# BLT_Preliminary_Avionics_Schematic_Brand.net
KiCad netlist of a schematic drawn in EAGLE
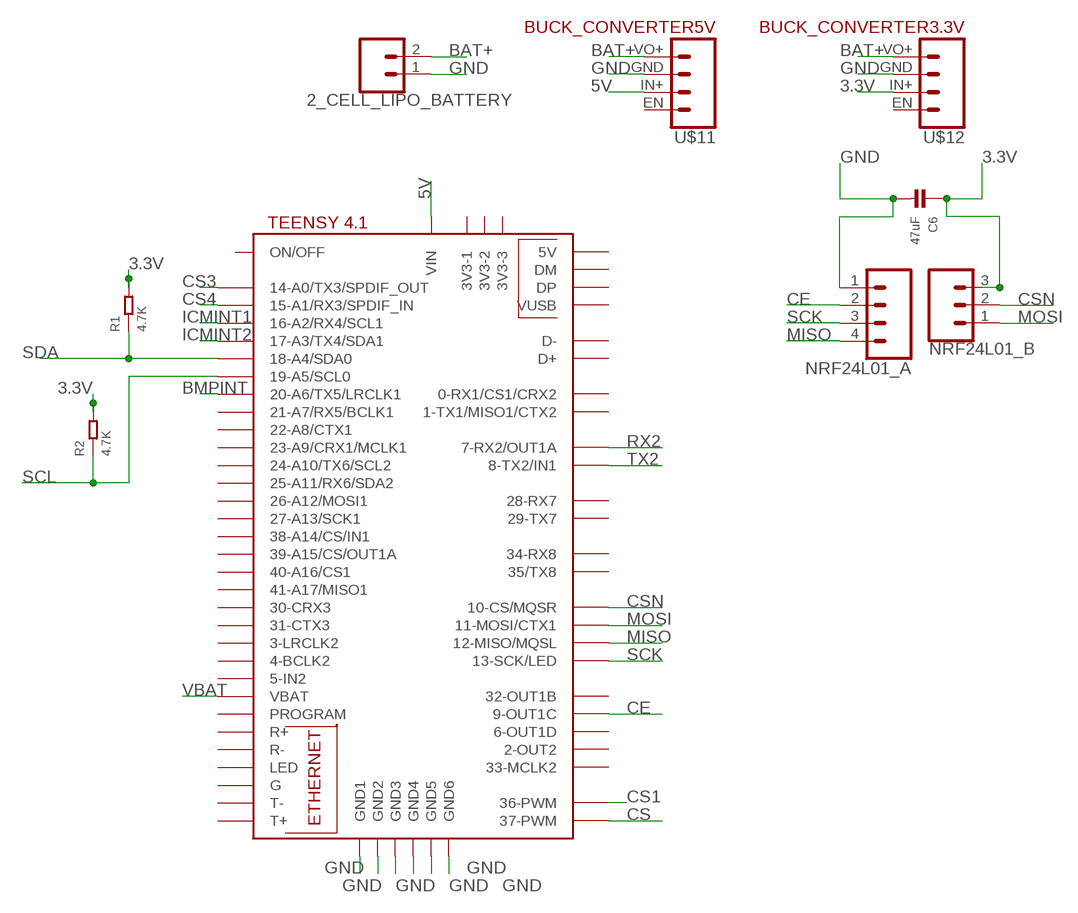
[diagram p0: schematic, sheet 1, part 1 of 2]
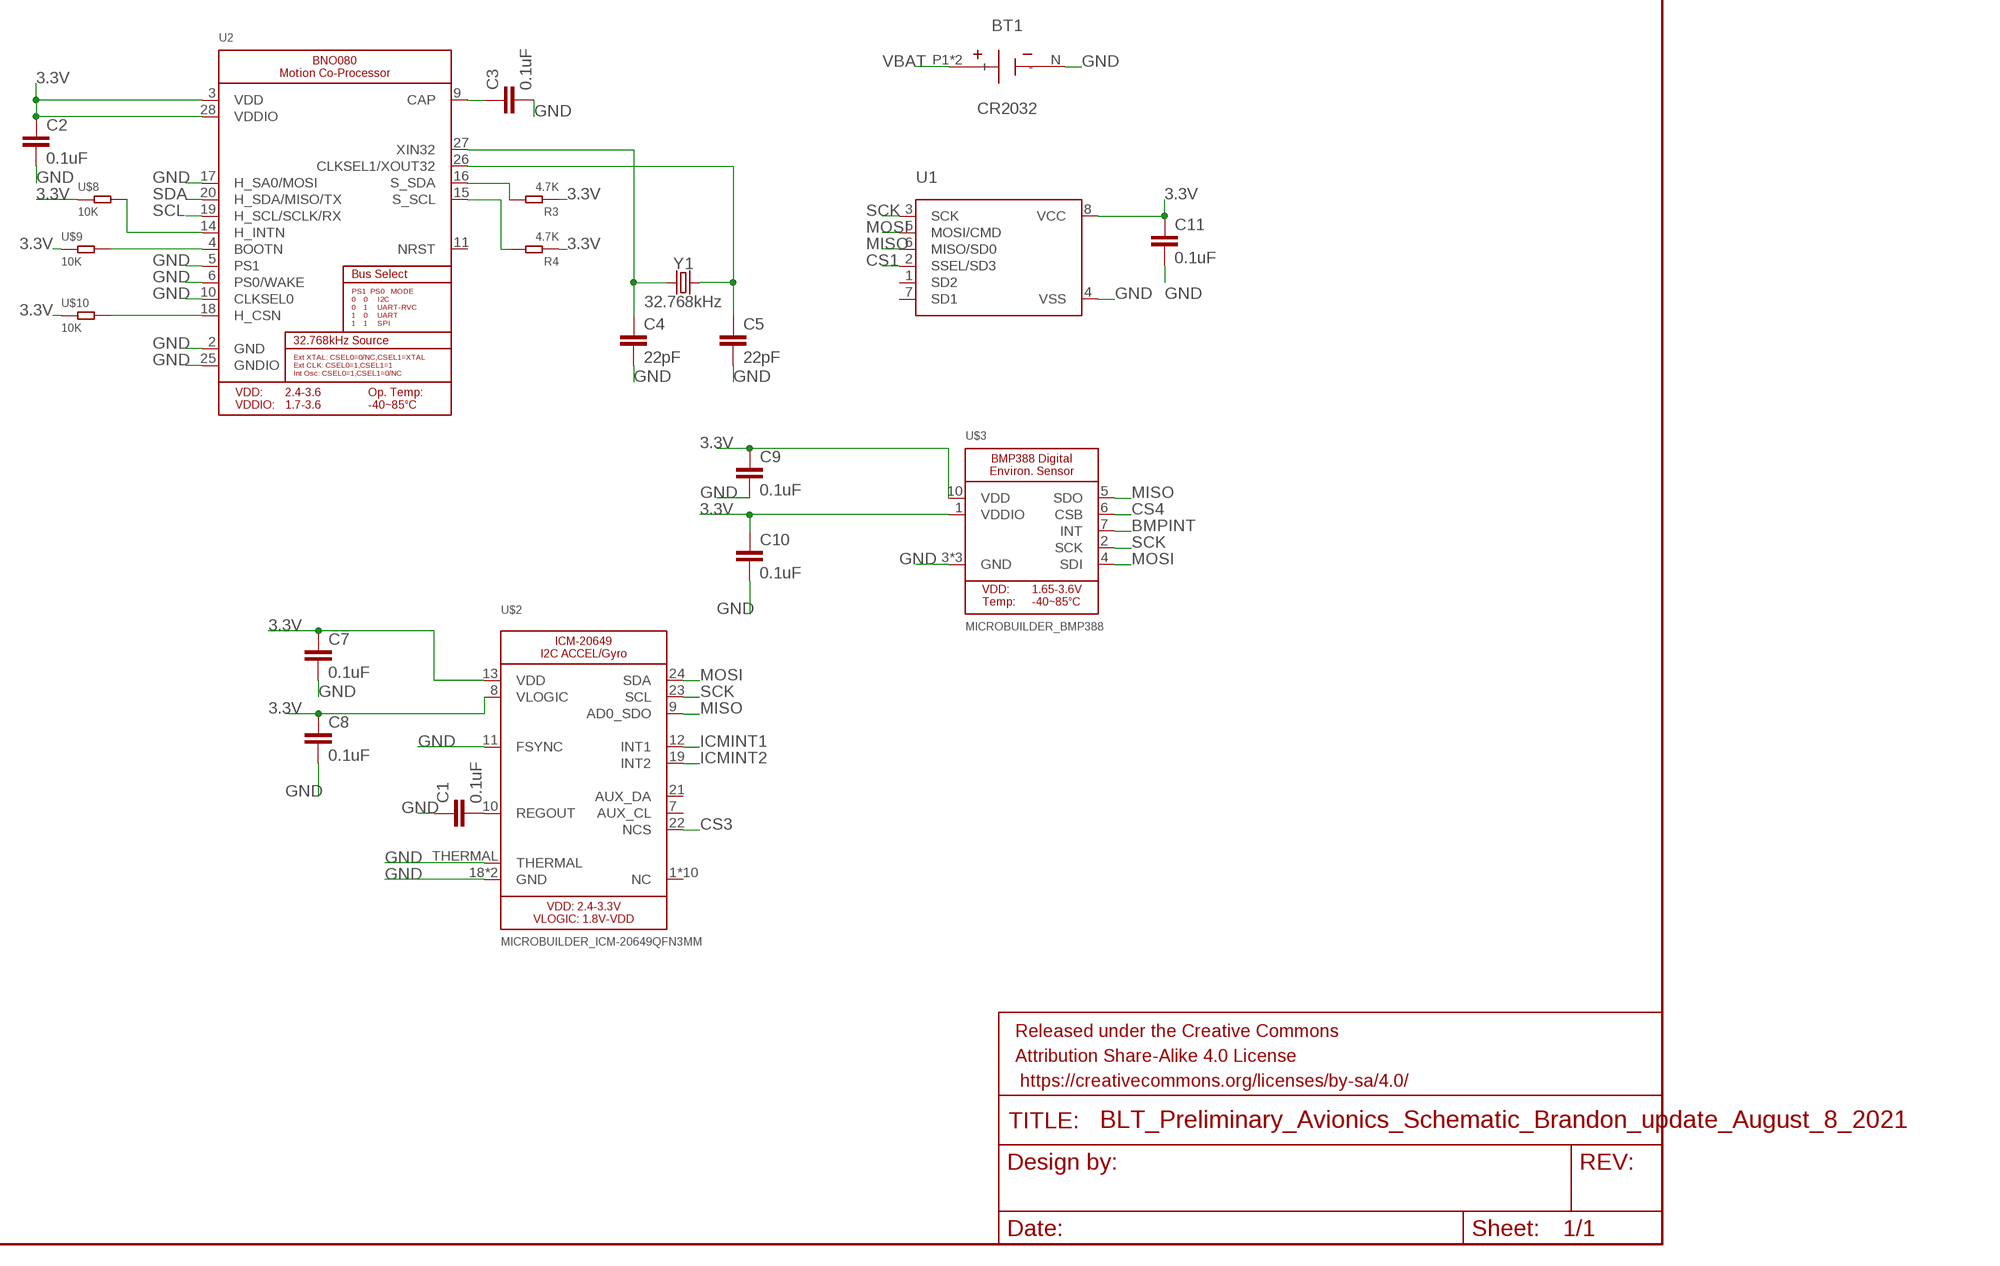
[diagram p1: schematic, sheet 1, part 2 of 2]

(export (version "E")
  (design (tool "Eeschema 10.0.6"))
  (components
    (comp (ref "2_CELL_LIPO_BATTERY")
      (value "CONN_02")
      (footprint "eagle-import:1X02")
      (libsource (lib "eagle-import") (part "CONN_02"))
    )
    (comp (ref "BT1")
      (value "CR2032")
      (footprint "eagle-import:BAT_3003")
      (fields (field (name "MANUFACTURER") "Keystone Electronics") (field (name "MPN") "3003"))
      (libsource (lib "eagle-import") (part "COIN-CELL-THM-3P?--3003CR2032"))
    )
    (comp (ref "C1")
      (value "0.1uF")
      (footprint "eagle-import:0402")
      (libsource (lib "eagle-import") (part "0.1UF-0402-16V-10%"))
    )
    (comp (ref "C2")
      (value "0.1uF")
      (footprint "eagle-import:0402")
      (libsource (lib "eagle-import") (part "0.1UF-0402-16V-10%"))
    )
    (comp (ref "C3")
      (value "0.1uF")
      (footprint "eagle-import:0402")
      (libsource (lib "eagle-import") (part "0.1UF-0402-16V-10%"))
    )
    (comp (ref "C4")
      (value "22pF")
      (footprint "eagle-import:0603")
      (libsource (lib "eagle-import") (part "22PF-0603-50V-5%"))
    )
    (comp (ref "C5")
      (value "22pF")
      (footprint "eagle-import:0603")
      (libsource (lib "eagle-import") (part "22PF-0603-50V-5%"))
    )
    (comp (ref "C6")
      (value "47uF")
      (footprint "eagle-import:0805")
      (libsource (lib "eagle-import") (part "CAP_CERAMIC0805"))
    )
    (comp (ref "C7")
      (value "0.1uF")
      (footprint "eagle-import:0603")
      (libsource (lib "eagle-import") (part "0.1UF-0603-100V-10%"))
    )
    (comp (ref "C8")
      (value "0.1uF")
      (footprint "eagle-import:0603")
      (libsource (lib "eagle-import") (part "0.1UF-0603-100V-10%"))
    )
    (comp (ref "C9")
      (value "0.1uF")
      (footprint "eagle-import:0603")
      (libsource (lib "eagle-import") (part "0.1UF-0603-100V-10%"))
    )
    (comp (ref "C10")
      (value "0.1uF")
      (footprint "eagle-import:0603")
      (libsource (lib "eagle-import") (part "0.1UF-0603-100V-10%"))
    )
    (comp (ref "C11")
      (value "0.1uF")
      (footprint "eagle-import:0603")
      (libsource (lib "eagle-import") (part "0.1UF-0603-100V-10%"))
    )
    (comp (ref "FRAME1")
      (value "FRAME-LEDGER")
      (footprint "eagle-import:CREATIVE_COMMONS")
      (libsource (lib "eagle-import") (part "FRAME-LEDGER"))
    )
    (comp (ref "NRF24L01_A")
      (value "CONN_04")
      (footprint "eagle-import:1X04")
      (libsource (lib "eagle-import") (part "CONN_04"))
    )
    (comp (ref "NRF24L01_B")
      (value "CONN_03")
      (footprint "eagle-import:1X03")
      (libsource (lib "eagle-import") (part "CONN_03"))
    )
    (comp (ref "R1")
      (value "4.7K")
      (footprint "eagle-import:R0402")
      (fields (field (name "MPN") "RC0402JR-074K7L"))
      (libsource (lib "eagle-import") (part "SMD-RES-4.7K-5%-1/16W(0402)"))
    )
    (comp (ref "R2")
      (value "4.7K")
      (footprint "eagle-import:R0402")
      (fields (field (name "MPN") "RC0402JR-074K7L"))
      (libsource (lib "eagle-import") (part "SMD-RES-4.7K-5%-1/16W(0402)"))
    )
    (comp (ref "R3")
      (value "4.7K")
      (footprint "eagle-import:R0402")
      (fields (field (name "MPN") "RC0402JR-074K7L"))
      (libsource (lib "eagle-import") (part "SMD-RES-4.7K-5%-1/16W(0402)"))
    )
    (comp (ref "R4")
      (value "4.7K")
      (footprint "eagle-import:R0402")
      (fields (field (name "MPN") "RC0402JR-074K7L"))
      (libsource (lib "eagle-import") (part "SMD-RES-4.7K-5%-1/16W(0402)"))
    )
    (comp (ref "U$1")
      (value "TEENSY41")
      (footprint "eagle-import:TEENSY41")
      (libsource (lib "eagle-import") (part "TEENSY41"))
    )
    (comp (ref "U$2")
      (value "MICROBUILDER_ICM-20649QFN3MM")
      (footprint "eagle-import:MICROBUILDER_QFN24_3MM")
      (libsource (lib "eagle-import") (part "MICROBUILDER_ICM-20649QFN3MM"))
    )
    (comp (ref "U$3")
      (value "MICROBUILDER_BMP388")
      (footprint "eagle-import:MICROBUILDER_BMP388")
      (libsource (lib "eagle-import") (part "MICROBUILDER_BMP388"))
    )
    (comp (ref "U$8")
      (value "10K")
      (footprint "eagle-import:R0402")
      (fields (field (name "MPN") "RC0402JR-0710KL"))
      (libsource (lib "eagle-import") (part "SMD-RES-10K-5%-1/(0402)"))
    )
    (comp (ref "U$9")
      (value "10K")
      (footprint "eagle-import:R0402")
      (fields (field (name "MPN") "RC0402JR-0710KL"))
      (libsource (lib "eagle-import") (part "SMD-RES-10K-5%-1/(0402)"))
    )
    (comp (ref "U$10")
      (value "10K")
      (footprint "eagle-import:R0402")
      (fields (field (name "MPN") "RC0402JR-0710KL"))
      (libsource (lib "eagle-import") (part "SMD-RES-10K-5%-1/(0402)"))
    )
    (comp (ref "U$11")
      (value "BUCK_CONVERTER5V")
      (footprint "eagle-import:1X04")
      (fields (field (name "VOLTAGE") "5V"))
      (libsource (lib "eagle-import") (part "BUCK_CONVERTER5V"))
    )
    (comp (ref "U$12")
      (value "BUCK_CONVERTER3.3V")
      (footprint "eagle-import:1X04")
      (fields (field (name "VOLTAGE") "3.3V"))
      (libsource (lib "eagle-import") (part "BUCK_CONVERTER3.3V"))
    )
    (comp (ref "U1")
      (value "MICROBUILDER_SMT_SDCARD_8PIN")
      (footprint "eagle-import:MICROBUILDER_LGA8_8X6")
      (libsource (lib "eagle-import") (part "MICROBUILDER_SMT_SDCARD_8PIN"))
    )
    (comp (ref "U2")
      (value "MICROBUILDER_BNO080")
      (footprint "eagle-import:MICROBUILDER_BNO080")
      (libsource (lib "eagle-import") (part "MICROBUILDER_BNO080"))
    )
    (comp (ref "Y1")
      (value "32.768kHz")
      (footprint "eagle-import:CRYSTAL-SMD-3.2X1.5MM")
      (libsource (lib "eagle-import") (part "CRYSTAL-32.768KHZSMD-3.2X1.5"))
    )
  )
  (nets
    (net (code "1") (name "/3.3V") (class "Default")
      (node (ref "C10") (pin "1") (pinfunction "1_1") (pintype "passive"))
      (node (ref "C11") (pin "1") (pinfunction "1_1") (pintype "passive"))
      (node (ref "C2") (pin "1") (pinfunction "1_1") (pintype "passive"))
      (node (ref "C6") (pin "1") (pinfunction "P$1_1") (pintype "passive"))
      (node (ref "C7") (pin "1") (pinfunction "1_1") (pintype "passive"))
      (node (ref "C8") (pin "1") (pinfunction "1_1") (pintype "passive"))
      (node (ref "C9") (pin "1") (pinfunction "1_1") (pintype "passive"))
      (node (ref "NRF24L01_B") (pin "3") (pinfunction "3_3") (pintype "passive"))
      (node (ref "R1") (pin "2") (pinfunction "2_2") (pintype "passive"))
      (node (ref "R2") (pin "2") (pinfunction "2_2") (pintype "passive"))
      (node (ref "R3") (pin "1") (pinfunction "1_1") (pintype "passive"))
      (node (ref "R4") (pin "1") (pinfunction "1_1") (pintype "passive"))
      (node (ref "U$10") (pin "1") (pinfunction "1_1") (pintype "passive"))
      (node (ref "U$12") (pin "IN+") (pinfunction "IN+_IN+") (pintype "passive"))
      (node (ref "U$2") (pin "13") (pinfunction "VDD_13") (pintype "power_in"))
      (node (ref "U$2") (pin "8") (pinfunction "VLOGIC_8") (pintype "power_in"))
      (node (ref "U$3") (pin "1") (pinfunction "VDDIO_1") (pintype "power_in"))
      (node (ref "U$3") (pin "10") (pinfunction "VDD_10") (pintype "power_in"))
      (node (ref "U$8") (pin "1") (pinfunction "1_1") (pintype "passive"))
      (node (ref "U$9") (pin "1") (pinfunction "1_1") (pintype "passive"))
      (node (ref "U1") (pin "8") (pinfunction "VCC_8") (pintype "power_in"))
      (node (ref "U2") (pin "28") (pinfunction "VDDIO_28") (pintype "power_in"))
      (node (ref "U2") (pin "3") (pinfunction "VDD_3") (pintype "power_in"))
    )
    (net (code "2") (name "/5V") (class "Default")
      (node (ref "U$1") (pin "VIN") (pinfunction "VIN_VIN") (pintype "bidirectional"))
      (node (ref "U$11") (pin "IN+") (pinfunction "IN+_IN+") (pintype "passive"))
    )
    (net (code "3") (name "/BAT+") (class "Default")
      (node (ref "2_CELL_LIPO_BATTERY") (pin "2") (pinfunction "2_2") (pintype "passive"))
      (node (ref "U$11") (pin "VO+") (pinfunction "VO+_VO+") (pintype "passive"))
      (node (ref "U$12") (pin "VO+") (pinfunction "VO+_VO+") (pintype "passive"))
    )
    (net (code "4") (name "/BMPINT") (class "Default")
      (node (ref "U$1") (pin "20-A6/TX5/LRCLK1") (pinfunction "20-A6/TX5/LRCLK1_20-A6/TX5/LRCLK1") (pintype "bidirectional"))
      (node (ref "U$3") (pin "7") (pinfunction "INT_7") (pintype "output"))
    )
    (net (code "5") (name "/CE") (class "Default")
      (node (ref "NRF24L01_A") (pin "2") (pinfunction "2_2") (pintype "passive"))
      (node (ref "U$1") (pin "9-OUT1C") (pinfunction "9-OUT1C_9-OUT1C") (pintype "bidirectional"))
    )
    (net (code "6") (name "/CS") (class "Default")
      (node (ref "U$1") (pin "37-PWM") (pinfunction "37-PWM_37-PWM") (pintype "bidirectional"))
    )
    (net (code "7") (name "/CS1") (class "Default")
      (node (ref "U$1") (pin "36-PWM") (pinfunction "36-PWM_36-PWM") (pintype "bidirectional"))
      (node (ref "U1") (pin "2") (pinfunction "SSEL/SD3_2") (pintype "bidirectional"))
    )
    (net (code "8") (name "/CS3") (class "Default")
      (node (ref "U$1") (pin "14-A0/TX3/SPDIF_OUT") (pinfunction "14-A0/TX3/SPDIF_OUT_14-A0/TX3/SPDIF_OUT") (pintype "bidirectional"))
      (node (ref "U$2") (pin "22") (pinfunction "NCS_22") (pintype "input"))
    )
    (net (code "9") (name "/CS4") (class "Default")
      (node (ref "U$1") (pin "15-A1/RX3/SPDIF_IN") (pinfunction "15-A1/RX3/SPDIF_IN_15-A1/RX3/SPDIF_IN") (pintype "bidirectional"))
      (node (ref "U$3") (pin "6") (pinfunction "CSB_6") (pintype "input"))
    )
    (net (code "10") (name "/CSN") (class "Default")
      (node (ref "NRF24L01_B") (pin "2") (pinfunction "2_2") (pintype "passive"))
      (node (ref "U$1") (pin "10-CS\\MQSR") (pinfunction "10-CS/MQSR_10-CS\\MQSR") (pintype "bidirectional"))
    )
    (net (code "11") (name "/GND") (class "Default")
      (node (ref "2_CELL_LIPO_BATTERY") (pin "1") (pinfunction "1_1") (pintype "passive"))
      (node (ref "BT1") (pin "N") (pinfunction "-_N") (pintype "bidirectional"))
      (node (ref "C1") (pin "1") (pinfunction "1_1") (pintype "passive"))
      (node (ref "C10") (pin "2") (pinfunction "2_2") (pintype "passive"))
      (node (ref "C11") (pin "2") (pinfunction "2_2") (pintype "passive"))
      (node (ref "C2") (pin "2") (pinfunction "2_2") (pintype "passive"))
      (node (ref "C3") (pin "2") (pinfunction "2_2") (pintype "passive"))
      (node (ref "C4") (pin "2") (pinfunction "2_2") (pintype "passive"))
      (node (ref "C5") (pin "2") (pinfunction "2_2") (pintype "passive"))
      (node (ref "C6") (pin "2") (pinfunction "P$2_2") (pintype "passive"))
      (node (ref "C7") (pin "2") (pinfunction "2_2") (pintype "passive"))
      (node (ref "C8") (pin "2") (pinfunction "2_2") (pintype "passive"))
      (node (ref "C9") (pin "2") (pinfunction "2_2") (pintype "passive"))
      (node (ref "NRF24L01_A") (pin "1") (pinfunction "1_1") (pintype "passive"))
      (node (ref "U$1") (pin "GND1") (pinfunction "GND1_GND1") (pintype "bidirectional"))
      (node (ref "U$1") (pin "GND2") (pinfunction "GND2_GND2") (pintype "bidirectional"))
      (node (ref "U$1") (pin "GND3") (pinfunction "GND3_GND3") (pintype "bidirectional"))
      (node (ref "U$1") (pin "GND4") (pinfunction "GND4_GND4") (pintype "bidirectional"))
      (node (ref "U$1") (pin "GND5") (pinfunction "GND5_GND5") (pintype "bidirectional"))
      (node (ref "U$1") (pin "GND6") (pinfunction "GND6_GND6") (pintype "bidirectional"))
      (node (ref "U$11") (pin "GND") (pinfunction "GND_GND") (pintype "passive"))
      (node (ref "U$12") (pin "GND") (pinfunction "GND_GND") (pintype "passive"))
      (node (ref "U$2") (pin "11") (pinfunction "FSYNC_11") (pintype "input"))
      (node (ref "U$2") (pin "18") (pinfunction "GND_18") (pintype "power_in"))
      (node (ref "U$2") (pin "20") (pinfunction "GND_20") (pintype "power_in"))
      (node (ref "U$2") (pin "THERMAL") (pinfunction "THERMAL_THERMAL") (pintype "power_in"))
      (node (ref "U$3") (pin "3") (pinfunction "GND_3") (pintype "power_in"))
      (node (ref "U$3") (pin "8") (pinfunction "GND_8") (pintype "power_in"))
      (node (ref "U$3") (pin "9") (pinfunction "GND_9") (pintype "power_in"))
      (node (ref "U1") (pin "4") (pinfunction "VSS_4") (pintype "power_in"))
      (node (ref "U2") (pin "10") (pinfunction "CLKSEL0_10") (pintype "input"))
      (node (ref "U2") (pin "17") (pinfunction "H_SA0/MOSI_17") (pintype "output"))
      (node (ref "U2") (pin "2") (pinfunction "GND_2") (pintype "power_in"))
      (node (ref "U2") (pin "25") (pinfunction "GNDIO_25") (pintype "power_in"))
      (node (ref "U2") (pin "5") (pinfunction "PS1_5") (pintype "input"))
      (node (ref "U2") (pin "6") (pinfunction "PS0/WAKE_6") (pintype "input"))
    )
    (net (code "12") (name "/ICMINT1") (class "Default")
      (node (ref "U$1") (pin "16-A2/RX4/SCL1") (pinfunction "16-A2/RX4/SCL1_16-A2/RX4/SCL1") (pintype "bidirectional"))
      (node (ref "U$2") (pin "12") (pinfunction "INT1_12") (pintype "output"))
    )
    (net (code "13") (name "/ICMINT2") (class "Default")
      (node (ref "U$1") (pin "17-A3/TX4/SDA1") (pinfunction "17-A3/TX4/SDA1_17-A3/TX4/SDA1") (pintype "bidirectional"))
      (node (ref "U$2") (pin "19") (pinfunction "INT2_19") (pintype "output"))
    )
    (net (code "14") (name "/MISO") (class "Default")
      (node (ref "NRF24L01_A") (pin "4") (pinfunction "4_4") (pintype "passive"))
      (node (ref "U$1") (pin "12-MISO/MQSL") (pinfunction "12-MISO/MQSL_12-MISO/MQSL") (pintype "bidirectional"))
      (node (ref "U$2") (pin "9") (pinfunction "AD0_SDO_9") (pintype "input"))
      (node (ref "U$3") (pin "5") (pinfunction "SDO_5") (pintype "output"))
      (node (ref "U1") (pin "6") (pinfunction "MISO/SD0_6") (pintype "bidirectional"))
    )
    (net (code "15") (name "/MOSI") (class "Default")
      (node (ref "NRF24L01_B") (pin "1") (pinfunction "1_1") (pintype "passive"))
      (node (ref "U$1") (pin "11-MOSI/CTX1") (pinfunction "11-MOSI/CTX1_11-MOSI/CTX1") (pintype "bidirectional"))
      (node (ref "U$2") (pin "24") (pinfunction "SDA_24") (pintype "bidirectional"))
      (node (ref "U$3") (pin "4") (pinfunction "SDI_4") (pintype "input"))
      (node (ref "U1") (pin "5") (pinfunction "MOSI/CMD_5") (pintype "bidirectional"))
    )
    (net (code "16") (name "/RX2") (class "Default")
      (node (ref "U$1") (pin "7-RX2/OUT1A") (pinfunction "7-RX2/OUT1A_7-RX2/OUT1A") (pintype "bidirectional"))
    )
    (net (code "17") (name "/SCK") (class "Default")
      (node (ref "NRF24L01_A") (pin "3") (pinfunction "3_3") (pintype "passive"))
      (node (ref "U$1") (pin "13-SCK/LED") (pinfunction "13-SCK/LED_13-SCK/LED") (pintype "bidirectional"))
      (node (ref "U$2") (pin "23") (pinfunction "SCL_23") (pintype "bidirectional"))
      (node (ref "U$3") (pin "2") (pinfunction "SCK_2") (pintype "input"))
      (node (ref "U1") (pin "3") (pinfunction "SCK_3") (pintype "input"))
    )
    (net (code "18") (name "/SCL") (class "Default")
      (node (ref "R2") (pin "1") (pinfunction "1_1") (pintype "passive"))
      (node (ref "U$1") (pin "19-A5/SCL0") (pinfunction "19-A5/SCL0_19-A5/SCL0") (pintype "bidirectional"))
      (node (ref "U2") (pin "19") (pinfunction "H_SCL/SCLK/RX_19") (pintype "bidirectional"))
    )
    (net (code "19") (name "/SDA") (class "Default")
      (node (ref "R1") (pin "1") (pinfunction "1_1") (pintype "passive"))
      (node (ref "U$1") (pin "18-A4/SDA0") (pinfunction "18-A4/SDA0_18-A4/SDA0") (pintype "bidirectional"))
      (node (ref "U2") (pin "20") (pinfunction "H_SDA/MISO/TX_20") (pintype "bidirectional"))
    )
    (net (code "20") (name "/TX2") (class "Default")
      (node (ref "U$1") (pin "8-TX2/IN1") (pinfunction "8-TX2/IN1_8-TX2/IN1") (pintype "bidirectional"))
    )
    (net (code "21") (name "/VBAT") (class "Default")
      (node (ref "BT1") (pin "P1") (pinfunction "+_P1") (pintype "bidirectional"))
      (node (ref "BT1") (pin "P2") (pinfunction "+_P2") (pintype "bidirectional"))
      (node (ref "U$1") (pin "VBAT") (pinfunction "VBAT_VBAT") (pintype "bidirectional"))
    )
    (net (code "22") (name "Net-(U$2-REGOUT)") (class "Default")
      (node (ref "C1") (pin "2") (pinfunction "2_2") (pintype "passive"))
      (node (ref "U$2") (pin "10") (pinfunction "REGOUT_10") (pintype "passive"))
    )
    (net (code "23") (name "Net-(U2-BOOTN)") (class "Default")
      (node (ref "U$9") (pin "2") (pinfunction "2_2") (pintype "passive"))
      (node (ref "U2") (pin "4") (pinfunction "BOOTN_4") (pintype "input"))
    )
    (net (code "24") (name "Net-(U2-CAP)") (class "Default")
      (node (ref "C3") (pin "1") (pinfunction "1_1") (pintype "passive"))
      (node (ref "U2") (pin "9") (pinfunction "CAP_9") (pintype "passive"))
    )
    (net (code "25") (name "Net-(U2-CLKSEL1{slash}XOUT32)") (class "Default")
      (node (ref "C5") (pin "1") (pinfunction "1_1") (pintype "passive"))
      (node (ref "U2") (pin "26") (pinfunction "CLKSEL1/XOUT32_26") (pintype "output"))
      (node (ref "Y1") (pin "P$2") (pinfunction "2_P$2") (pintype "passive"))
    )
    (net (code "26") (name "Net-(U2-H_CSN)") (class "Default")
      (node (ref "U$10") (pin "2") (pinfunction "2_2") (pintype "passive"))
      (node (ref "U2") (pin "18") (pinfunction "H_CSN_18") (pintype "input"))
    )
    (net (code "27") (name "Net-(U2-H_INTN)") (class "Default")
      (node (ref "U$8") (pin "2") (pinfunction "2_2") (pintype "passive"))
      (node (ref "U2") (pin "14") (pinfunction "H_INTN_14") (pintype "output"))
    )
    (net (code "28") (name "Net-(U2-S_SCL)") (class "Default")
      (node (ref "R4") (pin "2") (pinfunction "2_2") (pintype "passive"))
      (node (ref "U2") (pin "15") (pinfunction "S_SCL_15") (pintype "bidirectional"))
    )
    (net (code "29") (name "Net-(U2-S_SDA)") (class "Default")
      (node (ref "R3") (pin "2") (pinfunction "2_2") (pintype "passive"))
      (node (ref "U2") (pin "16") (pinfunction "S_SDA_16") (pintype "bidirectional"))
    )
    (net (code "30") (name "Net-(U2-XIN32)") (class "Default")
      (node (ref "C4") (pin "1") (pinfunction "1_1") (pintype "passive"))
      (node (ref "U2") (pin "27") (pinfunction "XIN32_27") (pintype "input"))
      (node (ref "Y1") (pin "P$1") (pinfunction "1_P$1") (pintype "passive"))
    )
    (net (code "31") (name "unconnected-(U$1-5V-Pad+5V)") (class "Default")
      (node (ref "U$1") (pin "+5V") (pinfunction "5V_+5V") (pintype "bidirectional"))
    )
    (net (code "32") (name "unconnected-(U$1-35{slash}TX8-Pad35-TX8)") (class "Default")
      (node (ref "U$1") (pin "35-TX8") (pinfunction "35/TX8_35-TX8") (pintype "bidirectional"))
    )
    (net (code "33") (name "unconnected-(U$1-Pad0-RX1{slash}CS1{slash}CRX2)") (class "Default")
      (node (ref "U$1") (pin "0-RX1/CS1/CRX2") (pinfunction "0-RX1/CS1/CRX2_0-RX1/CS1/CRX2") (pintype "bidirectional"))
    )
    (net (code "34") (name "unconnected-(U$1-Pad1-TX1{slash}MISO1{slash}CTX2)") (class "Default")
      (node (ref "U$1") (pin "1-TX1/MISO1/CTX2") (pinfunction "1-TX1/MISO1/CTX2_1-TX1/MISO1/CTX2") (pintype "bidirectional"))
    )
    (net (code "35") (name "unconnected-(U$1-Pad2-OUT2)") (class "Default")
      (node (ref "U$1") (pin "2-OUT2") (pinfunction "2-OUT2_2-OUT2") (pintype "bidirectional"))
    )
    (net (code "36") (name "unconnected-(U$1-Pad3-LRCLK2)") (class "Default")
      (node (ref "U$1") (pin "3-LRCLK2") (pinfunction "3-LRCLK2_3-LRCLK2") (pintype "bidirectional"))
    )
    (net (code "37") (name "unconnected-(U$1-Pad3V3-1)") (class "Default")
      (node (ref "U$1") (pin "3V3-1") (pinfunction "3V3-1_3V3-1") (pintype "bidirectional"))
    )
    (net (code "38") (name "unconnected-(U$1-Pad3V3-2)") (class "Default")
      (node (ref "U$1") (pin "3V3-2") (pinfunction "3V3-2_3V3-2") (pintype "bidirectional"))
    )
    (net (code "39") (name "unconnected-(U$1-Pad3V3-3)") (class "Default")
      (node (ref "U$1") (pin "3V3-3") (pinfunction "3V3-3_3V3-3") (pintype "bidirectional"))
    )
    (net (code "40") (name "unconnected-(U$1-Pad4-BCLK2)") (class "Default")
      (node (ref "U$1") (pin "4-BCLK2") (pinfunction "4-BCLK2_4-BCLK2") (pintype "bidirectional"))
    )
    (net (code "41") (name "unconnected-(U$1-Pad5-IN2)") (class "Default")
      (node (ref "U$1") (pin "5-IN2") (pinfunction "5-IN2_5-IN2") (pintype "bidirectional"))
    )
    (net (code "42") (name "unconnected-(U$1-Pad6-OUT1D)") (class "Default")
      (node (ref "U$1") (pin "6-OUT1D") (pinfunction "6-OUT1D_6-OUT1D") (pintype "bidirectional"))
    )
    (net (code "43") (name "unconnected-(U$1-Pad21-A7{slash}RX5{slash}BCLK1)") (class "Default")
      (node (ref "U$1") (pin "21-A7/RX5/BCLK1") (pinfunction "21-A7/RX5/BCLK1_21-A7/RX5/BCLK1") (pintype "bidirectional"))
    )
    (net (code "44") (name "unconnected-(U$1-Pad22-A8{slash}CTX1)") (class "Default")
      (node (ref "U$1") (pin "22-A8/CTX1") (pinfunction "22-A8/CTX1_22-A8/CTX1") (pintype "bidirectional"))
    )
    (net (code "45") (name "unconnected-(U$1-Pad23-A9{slash}CRX1{slash}MCLK1)") (class "Default")
      (node (ref "U$1") (pin "23-A9/CRX1/MCLK1") (pinfunction "23-A9/CRX1/MCLK1_23-A9/CRX1/MCLK1") (pintype "bidirectional"))
    )
    (net (code "46") (name "unconnected-(U$1-Pad24-A10{slash}TX6{slash}SCL2)") (class "Default")
      (node (ref "U$1") (pin "24-A10/TX6/SCL2") (pinfunction "24-A10/TX6/SCL2_24-A10/TX6/SCL2") (pintype "bidirectional"))
    )
    (net (code "47") (name "unconnected-(U$1-Pad25-A11{slash}RX6{slash}SDA2)") (class "Default")
      (node (ref "U$1") (pin "25-A11/RX6/SDA2") (pinfunction "25-A11/RX6/SDA2_25-A11/RX6/SDA2") (pintype "bidirectional"))
    )
    (net (code "48") (name "unconnected-(U$1-Pad26-A12{slash}MOSI1)") (class "Default")
      (node (ref "U$1") (pin "26-A12/MOSI1") (pinfunction "26-A12/MOSI1_26-A12/MOSI1") (pintype "bidirectional"))
    )
    (net (code "49") (name "unconnected-(U$1-Pad27-A13{slash}SCK1)") (class "Default")
      (node (ref "U$1") (pin "27-A13/SCK1") (pinfunction "27-A13/SCK1_27-A13/SCK1") (pintype "bidirectional"))
    )
    (net (code "50") (name "unconnected-(U$1-Pad28-RX7)") (class "Default")
      (node (ref "U$1") (pin "28-RX7") (pinfunction "28-RX7_28-RX7") (pintype "bidirectional"))
    )
    (net (code "51") (name "unconnected-(U$1-Pad29-TX7)") (class "Default")
      (node (ref "U$1") (pin "29-TX7") (pinfunction "29-TX7_29-TX7") (pintype "bidirectional"))
    )
    (net (code "52") (name "unconnected-(U$1-Pad30-CRX3)") (class "Default")
      (node (ref "U$1") (pin "30-CRX3") (pinfunction "30-CRX3_30-CRX3") (pintype "bidirectional"))
    )
    (net (code "53") (name "unconnected-(U$1-Pad31-CTX3)") (class "Default")
      (node (ref "U$1") (pin "31-CTX3") (pinfunction "31-CTX3_31-CTX3") (pintype "bidirectional"))
    )
    (net (code "54") (name "unconnected-(U$1-Pad32-OUT1B)") (class "Default")
      (node (ref "U$1") (pin "32-OUT1B") (pinfunction "32-OUT1B_32-OUT1B") (pintype "bidirectional"))
    )
    (net (code "55") (name "unconnected-(U$1-Pad33-MCLK2)") (class "Default")
      (node (ref "U$1") (pin "33-MCLK2") (pinfunction "33-MCLK2_33-MCLK2") (pintype "bidirectional"))
    )
    (net (code "56") (name "unconnected-(U$1-Pad34-RX8)") (class "Default")
      (node (ref "U$1") (pin "34-RX8") (pinfunction "34-RX8_34-RX8") (pintype "bidirectional"))
    )
    (net (code "57") (name "unconnected-(U$1-Pad38-A14{slash}CS{slash}IN1)") (class "Default")
      (node (ref "U$1") (pin "38-A14/CS/IN1") (pinfunction "38-A14/CS/IN1_38-A14/CS/IN1") (pintype "bidirectional"))
    )
    (net (code "58") (name "unconnected-(U$1-Pad39-A15{slash}CS{slash}OUT1A)") (class "Default")
      (node (ref "U$1") (pin "39-A15/CS/OUT1A") (pinfunction "39-A15/CS/OUT1A_39-A15/CS/OUT1A") (pintype "bidirectional"))
    )
    (net (code "59") (name "unconnected-(U$1-Pad40-A16{slash}CS1)") (class "Default")
      (node (ref "U$1") (pin "40-A16/CS1") (pinfunction "40-A16/CS1_40-A16/CS1") (pintype "bidirectional"))
    )
    (net (code "60") (name "unconnected-(U$1-Pad41-A17{slash}MISO1)") (class "Default")
      (node (ref "U$1") (pin "41-A17/MISO1") (pinfunction "41-A17/MISO1_41-A17/MISO1") (pintype "bidirectional"))
    )
    (net (code "61") (name "unconnected-(U$1-PadD+)") (class "Default")
      (node (ref "U$1") (pin "D+") (pinfunction "D+_D+") (pintype "bidirectional"))
    )
    (net (code "62") (name "unconnected-(U$1-PadD-)") (class "Default")
      (node (ref "U$1") (pin "D-") (pinfunction "D-_D-") (pintype "bidirectional"))
    )
    (net (code "63") (name "unconnected-(U$1-PadDM)") (class "Default")
      (node (ref "U$1") (pin "DM") (pinfunction "DM_DM") (pintype "bidirectional"))
    )
    (net (code "64") (name "unconnected-(U$1-PadDP)") (class "Default")
      (node (ref "U$1") (pin "DP") (pinfunction "DP_DP") (pintype "bidirectional"))
    )
    (net (code "65") (name "unconnected-(U$1-PadG)") (class "Default")
      (node (ref "U$1") (pin "G") (pinfunction "G_G") (pintype "bidirectional"))
    )
    (net (code "66") (name "unconnected-(U$1-PadLED)") (class "Default")
      (node (ref "U$1") (pin "LED") (pinfunction "LED_LED") (pintype "bidirectional"))
    )
    (net (code "67") (name "unconnected-(U$1-PadON{slash}OFF)") (class "Default")
      (node (ref "U$1") (pin "ON/OFF") (pinfunction "ON/OFF_ON/OFF") (pintype "bidirectional"))
    )
    (net (code "68") (name "unconnected-(U$1-PadPROGRAM)") (class "Default")
      (node (ref "U$1") (pin "PROGRAM") (pinfunction "PROGRAM_PROGRAM") (pintype "bidirectional"))
    )
    (net (code "69") (name "unconnected-(U$1-PadR+)") (class "Default")
      (node (ref "U$1") (pin "R+") (pinfunction "R+_R+") (pintype "bidirectional"))
    )
    (net (code "70") (name "unconnected-(U$1-PadR-)") (class "Default")
      (node (ref "U$1") (pin "R-") (pinfunction "R-_R-") (pintype "bidirectional"))
    )
    (net (code "71") (name "unconnected-(U$1-PadT+)") (class "Default")
      (node (ref "U$1") (pin "T+") (pinfunction "T+_T+") (pintype "bidirectional"))
    )
    (net (code "72") (name "unconnected-(U$1-PadT-)") (class "Default")
      (node (ref "U$1") (pin "T-") (pinfunction "T-_T-") (pintype "bidirectional"))
    )
    (net (code "73") (name "unconnected-(U$1-PadVUSB)") (class "Default")
      (node (ref "U$1") (pin "VUSB") (pinfunction "VUSB_VUSB") (pintype "bidirectional"))
    )
    (net (code "74") (name "unconnected-(U$2-AUX_CL-Pad7)") (class "Default")
      (node (ref "U$2") (pin "7") (pinfunction "AUX_CL_7") (pintype "bidirectional"))
    )
    (net (code "75") (name "unconnected-(U$2-AUX_DA-Pad21)") (class "Default")
      (node (ref "U$2") (pin "21") (pinfunction "AUX_DA_21") (pintype "bidirectional"))
    )
    (net (code "76") (name "unconnected-(U$2-NC-Pad1)") (class "Default")
      (node (ref "U$2") (pin "1") (pinfunction "NC_1") (pintype "no_connect"))
    )
    (net (code "77") (name "unconnected-(U$2-NC-Pad2)") (class "Default")
      (node (ref "U$2") (pin "2") (pinfunction "NC_2") (pintype "no_connect"))
    )
    (net (code "78") (name "unconnected-(U$2-NC-Pad3)") (class "Default")
      (node (ref "U$2") (pin "3") (pinfunction "NC_3") (pintype "no_connect"))
    )
    (net (code "79") (name "unconnected-(U$2-NC-Pad4)") (class "Default")
      (node (ref "U$2") (pin "4") (pinfunction "NC_4") (pintype "no_connect"))
    )
    (net (code "80") (name "unconnected-(U$2-NC-Pad5)") (class "Default")
      (node (ref "U$2") (pin "5") (pinfunction "NC_5") (pintype "no_connect"))
    )
    (net (code "81") (name "unconnected-(U$2-NC-Pad6)") (class "Default")
      (node (ref "U$2") (pin "6") (pinfunction "NC_6") (pintype "no_connect"))
    )
    (net (code "82") (name "unconnected-(U$2-NC-Pad14)") (class "Default")
      (node (ref "U$2") (pin "14") (pinfunction "NC_14") (pintype "no_connect"))
    )
    (net (code "83") (name "unconnected-(U$2-NC-Pad15)") (class "Default")
      (node (ref "U$2") (pin "15") (pinfunction "NC_15") (pintype "no_connect"))
    )
    (net (code "84") (name "unconnected-(U$2-NC-Pad16)") (class "Default")
      (node (ref "U$2") (pin "16") (pinfunction "NC_16") (pintype "no_connect"))
    )
    (net (code "85") (name "unconnected-(U$2-NC-Pad17)") (class "Default")
      (node (ref "U$2") (pin "17") (pinfunction "NC_17") (pintype "no_connect"))
    )
    (net (code "86") (name "unconnected-(U$11-PadEN)") (class "Default")
      (node (ref "U$11") (pin "EN") (pinfunction "EN_EN") (pintype "passive"))
    )
    (net (code "87") (name "unconnected-(U$12-PadEN)") (class "Default")
      (node (ref "U$12") (pin "EN") (pinfunction "EN_EN") (pintype "passive"))
    )
    (net (code "88") (name "unconnected-(U1-SD1-Pad7)") (class "Default")
      (node (ref "U1") (pin "7") (pinfunction "SD1_7") (pintype "bidirectional"))
    )
    (net (code "89") (name "unconnected-(U1-SD2-Pad1)") (class "Default")
      (node (ref "U1") (pin "1") (pinfunction "SD2_1") (pintype "bidirectional"))
    )
    (net (code "90") (name "unconnected-(U2-NRST-Pad11)") (class "Default")
      (node (ref "U2") (pin "11") (pinfunction "NRST_11") (pintype "input"))
    )
  )
)
